# untitled.net
KiCad netlist of a schematic drawn in EAGLE
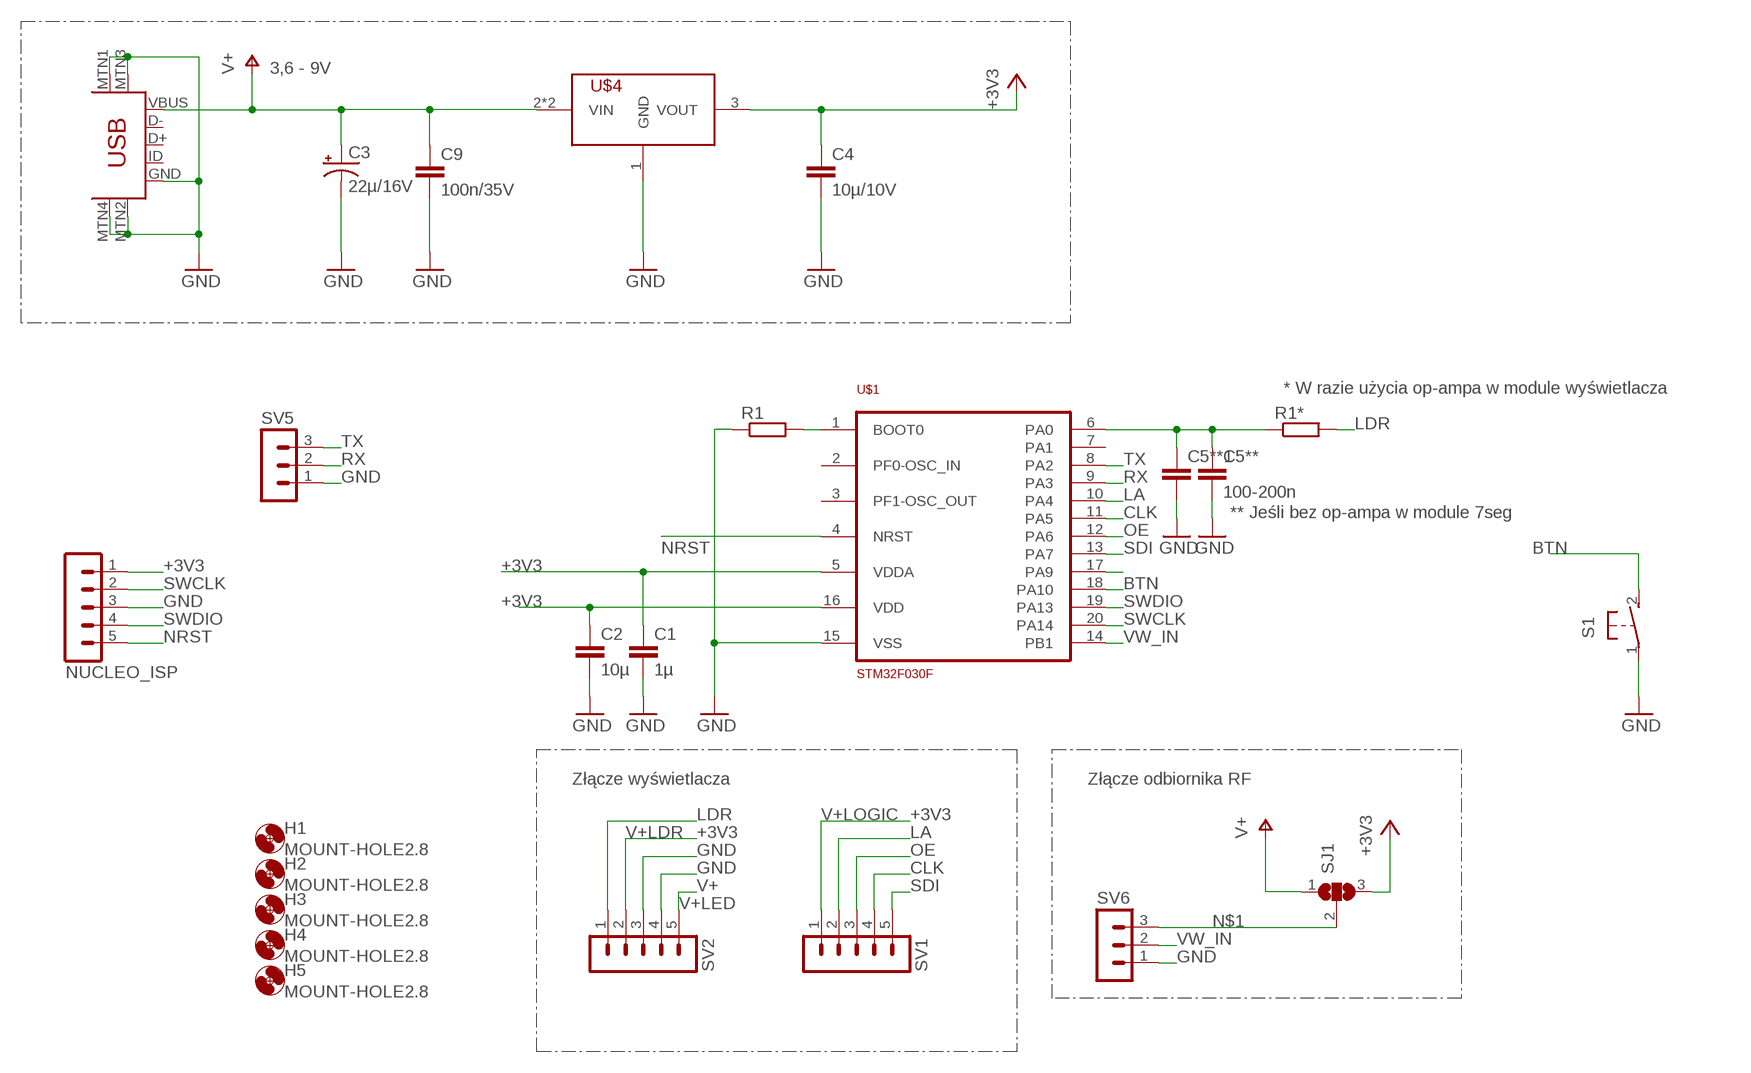
[diagram p0: schematic, sheet 1]

(export (version "E")
  (design (tool "Eeschema 10.0.6"))
  (components
    (comp (ref "C1")
      (value "1µ")
      (footprint "eagle-import:C0603")
      (libsource (lib "eagle-import") (part "C-EUC0603"))
    )
    (comp (ref "C2")
      (value "10µ")
      (footprint "eagle-import:C0603")
      (libsource (lib "eagle-import") (part "C-EUC0603"))
    )
    (comp (ref "C3")
      (value "22µ/16V")
      (footprint "eagle-import:E2,5-6")
      (libsource (lib "eagle-import") (part "CPOL-USE2.5-6"))
    )
    (comp (ref "C4")
      (value "10µ/10V")
      (footprint "eagle-import:C0603")
      (libsource (lib "eagle-import") (part "C-EUC0603"))
    )
    (comp (ref "C5**")
      (value "100-200n")
      (footprint "eagle-import:C0603")
      (libsource (lib "eagle-import") (part "C-EUC0603"))
    )
    (comp (ref "C5**1")
      (value "C-EUC0603")
      (footprint "eagle-import:C0603")
      (libsource (lib "eagle-import") (part "C-EUC0603"))
    )
    (comp (ref "C9")
      (value "100n/35V")
      (footprint "eagle-import:C0805")
      (libsource (lib "eagle-import") (part "C-EUC0805"))
    )
    (comp (ref "H1")
      (value "MOUNT-HOLE2.8")
      (footprint "eagle-import:2,8")
      (libsource (lib "eagle-import") (part "MOUNT-HOLE2.8"))
    )
    (comp (ref "H2")
      (value "MOUNT-HOLE2.8")
      (footprint "eagle-import:2,8")
      (libsource (lib "eagle-import") (part "MOUNT-HOLE2.8"))
    )
    (comp (ref "H3")
      (value "MOUNT-HOLE2.8")
      (footprint "eagle-import:2,8")
      (libsource (lib "eagle-import") (part "MOUNT-HOLE2.8"))
    )
    (comp (ref "H4")
      (value "MOUNT-HOLE2.8")
      (footprint "eagle-import:2,8")
      (libsource (lib "eagle-import") (part "MOUNT-HOLE2.8"))
    )
    (comp (ref "H5")
      (value "MOUNT-HOLE2.8")
      (footprint "eagle-import:2,8")
      (libsource (lib "eagle-import") (part "MOUNT-HOLE2.8"))
    )
    (comp (ref "NUCLEO_ISP")
      (value "MA05-1")
      (footprint "eagle-import:MA05-1")
      (libsource (lib "eagle-import") (part "MA05-1"))
    )
    (comp (ref "R1")
      (value "R-EU_R0603")
      (footprint "eagle-import:R0603")
      (libsource (lib "eagle-import") (part "R-EU_R0603"))
    )
    (comp (ref "R1*")
      (value "R-EU_R0603")
      (footprint "eagle-import:R0603")
      (libsource (lib "eagle-import") (part "R-EU_R0603"))
    )
    (comp (ref "S1")
      (value "31-XX")
      (footprint "eagle-import:B3F-31XX")
      (fields (field (name "MPN") "B3F-3100"))
      (libsource (lib "eagle-import") (part "31-XX"))
    )
    (comp (ref "SJ1")
      (value "SJ2W")
      (footprint "eagle-import:SJ_2")
      (libsource (lib "eagle-import") (part "SJ2W"))
    )
    (comp (ref "SV1")
      (value "MA05-1")
      (footprint "eagle-import:MA05-1")
      (libsource (lib "eagle-import") (part "MA05-1"))
    )
    (comp (ref "SV2")
      (value "MA05-1")
      (footprint "eagle-import:MA05-1")
      (libsource (lib "eagle-import") (part "MA05-1"))
    )
    (comp (ref "SV5")
      (value "MA03-1")
      (footprint "eagle-import:MA03-1")
      (libsource (lib "eagle-import") (part "MA03-1"))
    )
    (comp (ref "SV6")
      (value "MA03-1")
      (footprint "eagle-import:MA03-1")
      (libsource (lib "eagle-import") (part "MA03-1"))
    )
    (comp (ref "U$1")
      (value "STM32F030F")
      (footprint "eagle-import:TSSOP20")
      (libsource (lib "eagle-import") (part "STM32F030F"))
    )
    (comp (ref "U$2")
      (value "USB-MINIB-5PIN")
      (footprint "eagle-import:USB-MINIB")
      (libsource (lib "eagle-import") (part "USB-MINIB-5PIN"))
    )
    (comp (ref "U$4")
      (value "HT7333")
      (footprint "eagle-import:SOT89")
      (libsource (lib "eagle-import") (part "HT7333"))
    )
  )
  (nets
    (net (code "1") (name "+3V3") (class "Default")
      (node (ref "C1") (pin "1") (pinfunction "1_1") (pintype "passive"))
      (node (ref "C2") (pin "1") (pinfunction "1_1") (pintype "passive"))
      (node (ref "C4") (pin "1") (pinfunction "1_1") (pintype "passive"))
      (node (ref "NUCLEO_ISP") (pin "1") (pinfunction "1_1") (pintype "passive"))
      (node (ref "SJ1") (pin "3") (pinfunction "3_3") (pintype "passive"))
      (node (ref "SV1") (pin "1") (pinfunction "1_1") (pintype "passive"))
      (node (ref "SV2") (pin "2") (pinfunction "2_2") (pintype "passive"))
      (node (ref "U$1") (pin "16") (pinfunction "VDD_16") (pintype "power_in"))
      (node (ref "U$1") (pin "5") (pinfunction "VDDA_5") (pintype "power_in"))
      (node (ref "U$4") (pin "3") (pinfunction "VOUT_3") (pintype "power_in"))
    )
    (net (code "2") (name "/BTN") (class "Default")
      (node (ref "S1") (pin "2") (pinfunction "S_2") (pintype "passive"))
      (node (ref "U$1") (pin "18") (pinfunction "PA10_18") (pintype "bidirectional"))
    )
    (net (code "3") (name "/CLK") (class "Default")
      (node (ref "SV1") (pin "4") (pinfunction "4_4") (pintype "passive"))
      (node (ref "U$1") (pin "11") (pinfunction "PA5_11") (pintype "bidirectional"))
    )
    (net (code "4") (name "/LA") (class "Default")
      (node (ref "SV1") (pin "2") (pinfunction "2_2") (pintype "passive"))
      (node (ref "U$1") (pin "10") (pinfunction "PA4_10") (pintype "bidirectional"))
    )
    (net (code "5") (name "/LDR") (class "Default")
      (node (ref "R1*") (pin "2") (pinfunction "2_2") (pintype "passive"))
      (node (ref "SV2") (pin "1") (pinfunction "1_1") (pintype "passive"))
    )
    (net (code "6") (name "/N$1") (class "Default")
      (node (ref "SJ1") (pin "2") (pinfunction "2_2") (pintype "passive"))
      (node (ref "SV6") (pin "3") (pinfunction "3_3") (pintype "passive"))
    )
    (net (code "7") (name "/NRST") (class "Default")
      (node (ref "NUCLEO_ISP") (pin "5") (pinfunction "5_5") (pintype "passive"))
      (node (ref "U$1") (pin "4") (pinfunction "NRST_4") (pintype "input"))
    )
    (net (code "8") (name "/OE") (class "Default")
      (node (ref "SV1") (pin "3") (pinfunction "3_3") (pintype "passive"))
      (node (ref "U$1") (pin "12") (pinfunction "PA6_12") (pintype "bidirectional"))
    )
    (net (code "9") (name "/RX") (class "Default")
      (node (ref "SV5") (pin "2") (pinfunction "2_2") (pintype "passive"))
      (node (ref "U$1") (pin "9") (pinfunction "PA3_9") (pintype "bidirectional"))
    )
    (net (code "10") (name "/SDI") (class "Default")
      (node (ref "SV1") (pin "5") (pinfunction "5_5") (pintype "passive"))
      (node (ref "U$1") (pin "13") (pinfunction "PA7_13") (pintype "bidirectional"))
    )
    (net (code "11") (name "/SWCLK") (class "Default")
      (node (ref "NUCLEO_ISP") (pin "2") (pinfunction "2_2") (pintype "passive"))
      (node (ref "U$1") (pin "20") (pinfunction "PA14_20") (pintype "bidirectional"))
    )
    (net (code "12") (name "/SWDIO") (class "Default")
      (node (ref "NUCLEO_ISP") (pin "4") (pinfunction "4_4") (pintype "passive"))
      (node (ref "U$1") (pin "19") (pinfunction "PA13_19") (pintype "bidirectional"))
    )
    (net (code "13") (name "/TX") (class "Default")
      (node (ref "SV5") (pin "3") (pinfunction "3_3") (pintype "passive"))
      (node (ref "U$1") (pin "8") (pinfunction "PA2_8") (pintype "bidirectional"))
    )
    (net (code "14") (name "/VW_IN") (class "Default")
      (node (ref "SV6") (pin "2") (pinfunction "2_2") (pintype "passive"))
      (node (ref "U$1") (pin "14") (pinfunction "PB1_14") (pintype "bidirectional"))
    )
    (net (code "15") (name "GND") (class "Default")
      (node (ref "C1") (pin "2") (pinfunction "2_2") (pintype "passive"))
      (node (ref "C2") (pin "2") (pinfunction "2_2") (pintype "passive"))
      (node (ref "C3") (pin "-") (pinfunction "-_-") (pintype "passive"))
      (node (ref "C4") (pin "2") (pinfunction "2_2") (pintype "passive"))
      (node (ref "C5**") (pin "2") (pinfunction "2_2") (pintype "passive"))
      (node (ref "C5**1") (pin "2") (pinfunction "2_2") (pintype "passive"))
      (node (ref "C9") (pin "2") (pinfunction "2_2") (pintype "passive"))
      (node (ref "NUCLEO_ISP") (pin "3") (pinfunction "3_3") (pintype "passive"))
      (node (ref "R1") (pin "1") (pinfunction "1_1") (pintype "passive"))
      (node (ref "S1") (pin "1") (pinfunction "P_1") (pintype "passive"))
      (node (ref "SV2") (pin "3") (pinfunction "3_3") (pintype "passive"))
      (node (ref "SV2") (pin "4") (pinfunction "4_4") (pintype "passive"))
      (node (ref "SV5") (pin "1") (pinfunction "1_1") (pintype "passive"))
      (node (ref "SV6") (pin "1") (pinfunction "1_1") (pintype "passive"))
      (node (ref "U$1") (pin "15") (pinfunction "VSS_15") (pintype "power_in"))
      (node (ref "U$2") (pin "GND") (pinfunction "GND_GND") (pintype "bidirectional"))
      (node (ref "U$2") (pin "MTN1") (pinfunction "MTN2_MTN1") (pintype "bidirectional"))
      (node (ref "U$2") (pin "MTN2") (pinfunction "MTN3_MTN2") (pintype "bidirectional"))
      (node (ref "U$2") (pin "MTN3") (pinfunction "MTN1_MTN3") (pintype "bidirectional"))
      (node (ref "U$2") (pin "MTN4") (pinfunction "MTN4_MTN4") (pintype "bidirectional"))
      (node (ref "U$4") (pin "1") (pinfunction "GND_1") (pintype "power_in"))
    )
    (net (code "16") (name "Net-(U$1-BOOT0)") (class "Default")
      (node (ref "R1") (pin "2") (pinfunction "2_2") (pintype "passive"))
      (node (ref "U$1") (pin "1") (pinfunction "BOOT0_1") (pintype "input"))
    )
    (net (code "17") (name "Net-(U$1-PA0)") (class "Default")
      (node (ref "C5**") (pin "1") (pinfunction "1_1") (pintype "passive"))
      (node (ref "C5**1") (pin "1") (pinfunction "1_1") (pintype "passive"))
      (node (ref "R1*") (pin "1") (pinfunction "1_1") (pintype "passive"))
      (node (ref "U$1") (pin "6") (pinfunction "PA0_6") (pintype "bidirectional"))
    )
    (net (code "18") (name "V+") (class "Default")
      (node (ref "C3") (pin "+") (pinfunction "+_+") (pintype "passive"))
      (node (ref "C9") (pin "1") (pinfunction "1_1") (pintype "passive"))
      (node (ref "SJ1") (pin "1") (pinfunction "1_1") (pintype "passive"))
      (node (ref "SV2") (pin "5") (pinfunction "5_5") (pintype "passive"))
      (node (ref "U$2") (pin "VBUS") (pinfunction "VBUS_VBUS") (pintype "bidirectional"))
      (node (ref "U$4") (pin "2") (pinfunction "VIN_2") (pintype "power_in"))
      (node (ref "U$4") (pin "2.1") (pinfunction "VIN_2.1") (pintype "power_in"))
    )
    (net (code "19") (name "unconnected-(U$1-PA1-Pad7)") (class "Default")
      (node (ref "U$1") (pin "7") (pinfunction "PA1_7") (pintype "bidirectional"))
    )
    (net (code "20") (name "unconnected-(U$1-PA9-Pad17)") (class "Default")
      (node (ref "U$1") (pin "17") (pinfunction "PA9_17") (pintype "bidirectional"))
    )
    (net (code "21") (name "unconnected-(U$1-PF0-OSC_IN-Pad2)") (class "Default")
      (node (ref "U$1") (pin "2") (pinfunction "PF0-OSC_IN_2") (pintype "bidirectional"))
    )
    (net (code "22") (name "unconnected-(U$1-PF1-OSC_OUT-Pad3)") (class "Default")
      (node (ref "U$1") (pin "3") (pinfunction "PF1-OSC_OUT_3") (pintype "bidirectional"))
    )
    (net (code "23") (name "unconnected-(U$2-PadD+)") (class "Default")
      (node (ref "U$2") (pin "D+") (pinfunction "D+_D+") (pintype "bidirectional"))
    )
    (net (code "24") (name "unconnected-(U$2-PadD-)") (class "Default")
      (node (ref "U$2") (pin "D-") (pinfunction "D-_D-") (pintype "bidirectional"))
    )
    (net (code "25") (name "unconnected-(U$2-PadID)") (class "Default")
      (node (ref "U$2") (pin "ID") (pinfunction "ID_ID") (pintype "bidirectional"))
    )
  )
)
